# remote_handmade.net
KiCad netlist of a schematic drawn in EAGLE
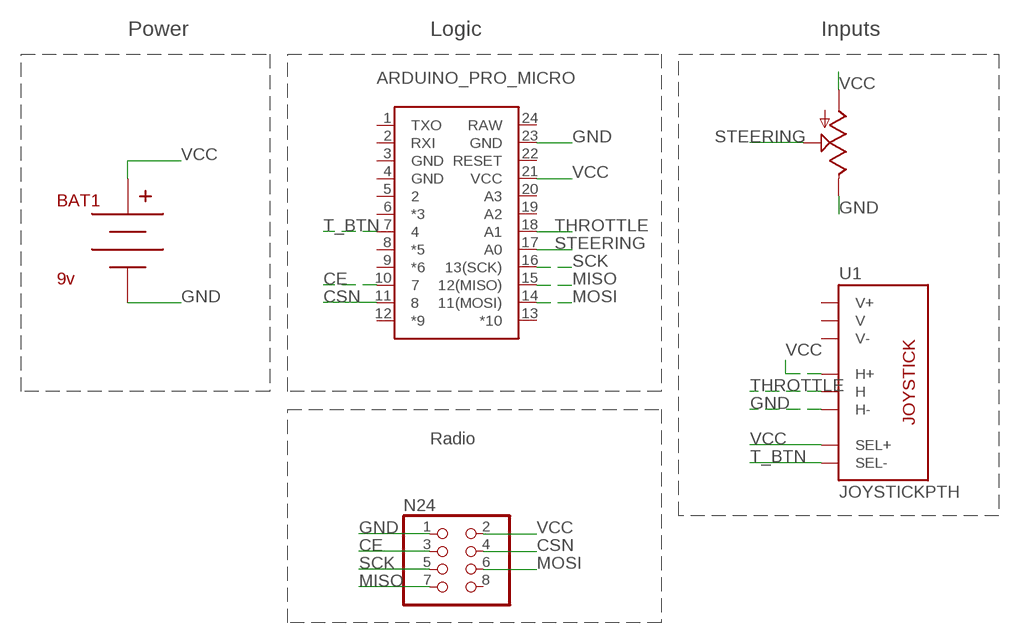
[diagram p0: schematic, sheet 1]

(export (version "E")
  (design (tool "Eeschema 10.0.6"))
  (components
    (comp (ref "ARDUINO_PRO_MICRO")
      (value "ARDUINO_PRO_MICRONORMALNORMAL")
      (footprint "eagle-import:ARDUINO_PRO_MICRO")
      (libsource (lib "eagle-import") (part "ARDUINO_PRO_MICRONORMALNORMAL"))
    )
    (comp (ref "BAT1")
      (value "9v")
      (footprint "eagle-import:BC9VPC")
      (libsource (lib "eagle-import") (part "BC9VPC"))
    )
    (comp (ref "N24")
      (value "NRF24")
      (footprint "eagle-import:2X04")
      (libsource (lib "eagle-import") (part "PINHD-2X4"))
    )
    (comp (ref "RV1")
      (value "POT")
      (footprint "eagle-import:ALPS_POT")
      (libsource (lib "eagle-import") (part "POT"))
    )
    (comp (ref "U1")
      (value "JOYSTICKPTH")
      (footprint "eagle-import:JOYSTICK")
      (libsource (lib "eagle-import") (part "JOYSTICKPTH"))
    )
  )
  (nets
    (net (code "1") (name "/CE") (class "Default")
      (node (ref "ARDUINO_PRO_MICRO") (pin "10") (pinfunction "7_10") (pintype "bidirectional"))
      (node (ref "N24") (pin "3") (pinfunction "3_3") (pintype "passive"))
    )
    (net (code "2") (name "/CSN") (class "Default")
      (node (ref "ARDUINO_PRO_MICRO") (pin "11") (pinfunction "8_11") (pintype "bidirectional"))
      (node (ref "N24") (pin "4") (pinfunction "4_4") (pintype "passive"))
    )
    (net (code "3") (name "/GND") (class "Default")
      (node (ref "ARDUINO_PRO_MICRO") (pin "23") (pinfunction "GND_23") (pintype "bidirectional"))
      (node (ref "BAT1") (pin "V-") (pinfunction "V-_V-") (pintype "bidirectional"))
      (node (ref "N24") (pin "1") (pinfunction "1_1") (pintype "passive"))
      (node (ref "RV1") (pin "P$1") (pinfunction "E_P$1") (pintype "passive"))
      (node (ref "U1") (pin "H3") (pinfunction "H-_H3") (pintype "bidirectional"))
    )
    (net (code "4") (name "/MISO") (class "Default")
      (node (ref "ARDUINO_PRO_MICRO") (pin "15") (pinfunction "12(MISO)_15") (pintype "bidirectional"))
      (node (ref "N24") (pin "7") (pinfunction "7_7") (pintype "passive"))
    )
    (net (code "5") (name "/MOSI") (class "Default")
      (node (ref "ARDUINO_PRO_MICRO") (pin "14") (pinfunction "11(MOSI)_14") (pintype "bidirectional"))
      (node (ref "N24") (pin "6") (pinfunction "6_6") (pintype "passive"))
    )
    (net (code "6") (name "/SCK") (class "Default")
      (node (ref "ARDUINO_PRO_MICRO") (pin "16") (pinfunction "13(SCK)_16") (pintype "bidirectional"))
      (node (ref "N24") (pin "5") (pinfunction "5_5") (pintype "passive"))
    )
    (net (code "7") (name "/STEERING") (class "Default")
      (node (ref "ARDUINO_PRO_MICRO") (pin "17") (pinfunction "A0_17") (pintype "bidirectional"))
      (node (ref "RV1") (pin "P$2") (pinfunction "S_P$2") (pintype "passive"))
    )
    (net (code "8") (name "/THROTTLE") (class "Default")
      (node (ref "ARDUINO_PRO_MICRO") (pin "18") (pinfunction "A1_18") (pintype "bidirectional"))
      (node (ref "U1") (pin "H2") (pinfunction "H_H2") (pintype "bidirectional"))
    )
    (net (code "9") (name "/T_BTN") (class "Default")
      (node (ref "ARDUINO_PRO_MICRO") (pin "7") (pinfunction "4_7") (pintype "bidirectional"))
      (node (ref "U1") (pin "B2A") (pinfunction "SEL-_B2A") (pintype "bidirectional"))
    )
    (net (code "10") (name "/VCC") (class "Default")
      (node (ref "ARDUINO_PRO_MICRO") (pin "21") (pinfunction "VCC_21") (pintype "bidirectional"))
      (node (ref "BAT1") (pin "V+") (pinfunction "V+_V+") (pintype "bidirectional"))
      (node (ref "N24") (pin "2") (pinfunction "2_2") (pintype "passive"))
      (node (ref "RV1") (pin "P$3") (pinfunction "A_P$3") (pintype "passive"))
      (node (ref "U1") (pin "B1A") (pinfunction "SEL+_B1A") (pintype "bidirectional"))
      (node (ref "U1") (pin "H1") (pinfunction "H+_H1") (pintype "bidirectional"))
    )
    (net (code "11") (name "unconnected-(ARDUINO_PRO_MICRO-*3-Pad6)") (class "Default")
      (node (ref "ARDUINO_PRO_MICRO") (pin "6") (pinfunction "*3_6") (pintype "bidirectional"))
    )
    (net (code "12") (name "unconnected-(ARDUINO_PRO_MICRO-*5-Pad8)") (class "Default")
      (node (ref "ARDUINO_PRO_MICRO") (pin "8") (pinfunction "*5_8") (pintype "bidirectional"))
    )
    (net (code "13") (name "unconnected-(ARDUINO_PRO_MICRO-*6-Pad9)") (class "Default")
      (node (ref "ARDUINO_PRO_MICRO") (pin "9") (pinfunction "*6_9") (pintype "bidirectional"))
    )
    (net (code "14") (name "unconnected-(ARDUINO_PRO_MICRO-*9-Pad12)") (class "Default")
      (node (ref "ARDUINO_PRO_MICRO") (pin "12") (pinfunction "*9_12") (pintype "bidirectional"))
    )
    (net (code "15") (name "unconnected-(ARDUINO_PRO_MICRO-*10-Pad13)") (class "Default")
      (node (ref "ARDUINO_PRO_MICRO") (pin "13") (pinfunction "*10_13") (pintype "bidirectional"))
    )
    (net (code "16") (name "unconnected-(ARDUINO_PRO_MICRO-2-Pad5)") (class "Default")
      (node (ref "ARDUINO_PRO_MICRO") (pin "5") (pinfunction "2_5") (pintype "bidirectional"))
    )
    (net (code "17") (name "unconnected-(ARDUINO_PRO_MICRO-A2-Pad19)") (class "Default")
      (node (ref "ARDUINO_PRO_MICRO") (pin "19") (pinfunction "A2_19") (pintype "bidirectional"))
    )
    (net (code "18") (name "unconnected-(ARDUINO_PRO_MICRO-A3-Pad20)") (class "Default")
      (node (ref "ARDUINO_PRO_MICRO") (pin "20") (pinfunction "A3_20") (pintype "bidirectional"))
    )
    (net (code "19") (name "unconnected-(ARDUINO_PRO_MICRO-GND-Pad3)") (class "Default")
      (node (ref "ARDUINO_PRO_MICRO") (pin "3") (pinfunction "GND_3") (pintype "bidirectional"))
    )
    (net (code "20") (name "unconnected-(ARDUINO_PRO_MICRO-GND-Pad4)") (class "Default")
      (node (ref "ARDUINO_PRO_MICRO") (pin "4") (pinfunction "GND_4") (pintype "bidirectional"))
    )
    (net (code "21") (name "unconnected-(ARDUINO_PRO_MICRO-RAW-Pad24)") (class "Default")
      (node (ref "ARDUINO_PRO_MICRO") (pin "24") (pinfunction "RAW_24") (pintype "bidirectional"))
    )
    (net (code "22") (name "unconnected-(ARDUINO_PRO_MICRO-RESET-Pad22)") (class "Default")
      (node (ref "ARDUINO_PRO_MICRO") (pin "22") (pinfunction "RESET_22") (pintype "bidirectional"))
    )
    (net (code "23") (name "unconnected-(ARDUINO_PRO_MICRO-RXI-Pad2)") (class "Default")
      (node (ref "ARDUINO_PRO_MICRO") (pin "2") (pinfunction "RXI_2") (pintype "bidirectional"))
    )
    (net (code "24") (name "unconnected-(ARDUINO_PRO_MICRO-TXO-Pad1)") (class "Default")
      (node (ref "ARDUINO_PRO_MICRO") (pin "1") (pinfunction "TXO_1") (pintype "bidirectional"))
    )
    (net (code "25") (name "unconnected-(N24-Pad8)") (class "Default")
      (node (ref "N24") (pin "8") (pinfunction "8_8") (pintype "passive"))
    )
    (net (code "26") (name "unconnected-(U1-V+-PadV1)") (class "Default")
      (node (ref "U1") (pin "V1") (pinfunction "V+_V1") (pintype "bidirectional"))
    )
    (net (code "27") (name "unconnected-(U1-V--PadV3)") (class "Default")
      (node (ref "U1") (pin "V3") (pinfunction "V-_V3") (pintype "bidirectional"))
    )
    (net (code "28") (name "unconnected-(U1-V-PadV2)") (class "Default")
      (node (ref "U1") (pin "V2") (pinfunction "V_V2") (pintype "bidirectional"))
    )
  )
)
